# Sheet_DC.net
KiCad netlist of a schematic drawn in Altium Designer
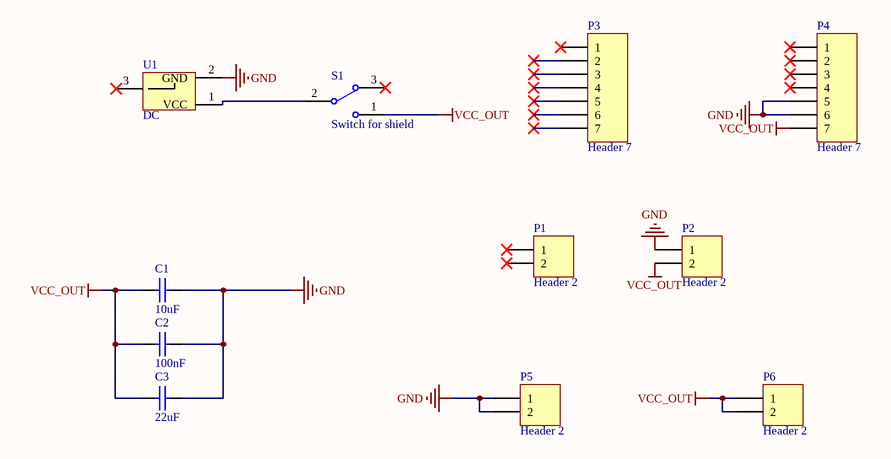
[diagram p0: Sheet_DC.SchDoc]

(export (version "E")
  (design (tool "Eeschema 10.0.6"))
  (components
    (comp (ref "C1")
      (value "10uF")
      (footprint "C0603")
      (description "贴片电容")
      (libsource (lib "Schlib_OLEDMCU") (part "C0603"))
    )
    (comp (ref "C2")
      (value "100nF")
      (footprint "C0603")
      (description "贴片电容")
      (libsource (lib "Schlib_OLEDMCU") (part "C0603"))
    )
    (comp (ref "C3")
      (value "22uF")
      (footprint "C0603")
      (description "贴片电容")
      (libsource (lib "Schlib_OLEDMCU") (part "C0603"))
    )
    (comp (ref "P1")
      (value "Header 2")
      (footprint "HDR1X2")
      (description "Header, 2-Pin")
      (fields (field (name "PUBLISHER") "Altium Limited"))
      (libsource (lib "Miscellaneous Connectors") (part "Header 2"))
    )
    (comp (ref "P2")
      (value "Header 2")
      (footprint "HDR1X2")
      (description "Header, 2-Pin")
      (fields (field (name "PUBLISHER") "Altium Limited"))
      (libsource (lib "Miscellaneous Connectors") (part "Header 2"))
    )
    (comp (ref "P3")
      (value "Header 7")
      (footprint "HDR1X7")
      (description "Header, 7-Pin")
      (fields (field (name "PUBLISHER") "Altium Limited"))
      (libsource (lib "Miscellaneous Connectors") (part "Header 7"))
    )
    (comp (ref "P4")
      (value "Header 7")
      (footprint "HDR1X7")
      (description "Header, 7-Pin")
      (fields (field (name "PUBLISHER") "Altium Limited"))
      (libsource (lib "Miscellaneous Connectors") (part "Header 7"))
    )
    (comp (ref "P5")
      (value "Header 2")
      (footprint "HDR1X2")
      (description "Header, 2-Pin")
      (fields (field (name "PUBLISHER") "Altium Limited"))
      (libsource (lib "Miscellaneous Connectors") (part "Header 2"))
    )
    (comp (ref "P6")
      (value "Header 2")
      (footprint "HDR1X2")
      (description "Header, 2-Pin")
      (fields (field (name "PUBLISHER") "Altium Limited"))
      (libsource (lib "Miscellaneous Connectors") (part "Header 2"))
    )
    (comp (ref "S1")
      (value "Switch for shield")
      (footprint "Switch_battery")
      (description "三脚开关")
      (libsource (lib "Schlib_OLEDMCU") (part "Switch_battery"))
    )
    (comp (ref "U1")
      (value "DC")
      (footprint "DC")
      (description "DC插座")
      (libsource (lib "Schlib_OLEDMCU") (part "DC"))
    )
  )
  (nets
    (net (code "1") (name "GND") (class "Default")
      (node (ref "C1") (pin "2") (pinfunction "2_2") (pintype "passive"))
      (node (ref "C2") (pin "2") (pinfunction "2_2") (pintype "passive"))
      (node (ref "C3") (pin "2") (pinfunction "2_2") (pintype "passive"))
      (node (ref "P2") (pin "1") (pinfunction "1_1") (pintype "passive"))
      (node (ref "P4") (pin "5") (pinfunction "5_5") (pintype "passive"))
      (node (ref "P4") (pin "6") (pinfunction "6_6") (pintype "passive"))
      (node (ref "P5") (pin "1") (pinfunction "1_1") (pintype "passive"))
      (node (ref "P5") (pin "2") (pinfunction "2_2") (pintype "passive"))
      (node (ref "U1") (pin "2") (pinfunction "GND_2") (pintype "passive"))
    )
    (net (code "2") (name "Net-(U1-VCC)") (class "Default")
      (node (ref "S1") (pin "2") (pinfunction "2_2") (pintype "passive"))
      (node (ref "U1") (pin "1") (pinfunction "VCC_1") (pintype "passive"))
    )
    (net (code "3") (name "VCC_OUT") (class "Default")
      (node (ref "C1") (pin "1") (pinfunction "1_1") (pintype "passive"))
      (node (ref "C2") (pin "1") (pinfunction "1_1") (pintype "passive"))
      (node (ref "C3") (pin "1") (pinfunction "1_1") (pintype "passive"))
      (node (ref "P2") (pin "2") (pinfunction "2_2") (pintype "passive"))
      (node (ref "P4") (pin "7") (pinfunction "7_7") (pintype "passive"))
      (node (ref "P6") (pin "1") (pinfunction "1_1") (pintype "passive"))
      (node (ref "P6") (pin "2") (pinfunction "2_2") (pintype "passive"))
      (node (ref "S1") (pin "1") (pinfunction "1_1") (pintype "passive"))
    )
    (net (code "4") (name "unconnected-(P1-Pad1)") (class "Default")
      (node (ref "P1") (pin "1") (pinfunction "1_1") (pintype "passive+no_connect"))
    )
    (net (code "5") (name "unconnected-(P1-Pad2)") (class "Default")
      (node (ref "P1") (pin "2") (pinfunction "2_2") (pintype "passive+no_connect"))
    )
    (net (code "6") (name "unconnected-(P3-Pad1)") (class "Default")
      (node (ref "P3") (pin "1") (pinfunction "1_1") (pintype "passive+no_connect"))
    )
    (net (code "7") (name "unconnected-(P3-Pad2)") (class "Default")
      (node (ref "P3") (pin "2") (pinfunction "2_2") (pintype "passive+no_connect"))
    )
    (net (code "8") (name "unconnected-(P3-Pad3)") (class "Default")
      (node (ref "P3") (pin "3") (pinfunction "3_3") (pintype "passive+no_connect"))
    )
    (net (code "9") (name "unconnected-(P3-Pad4)") (class "Default")
      (node (ref "P3") (pin "4") (pinfunction "4_4") (pintype "passive+no_connect"))
    )
    (net (code "10") (name "unconnected-(P3-Pad5)") (class "Default")
      (node (ref "P3") (pin "5") (pinfunction "5_5") (pintype "passive+no_connect"))
    )
    (net (code "11") (name "unconnected-(P3-Pad6)") (class "Default")
      (node (ref "P3") (pin "6") (pinfunction "6_6") (pintype "passive+no_connect"))
    )
    (net (code "12") (name "unconnected-(P3-Pad7)") (class "Default")
      (node (ref "P3") (pin "7") (pinfunction "7_7") (pintype "passive+no_connect"))
    )
    (net (code "13") (name "unconnected-(P4-Pad1)") (class "Default")
      (node (ref "P4") (pin "1") (pinfunction "1_1") (pintype "passive+no_connect"))
    )
    (net (code "14") (name "unconnected-(P4-Pad2)") (class "Default")
      (node (ref "P4") (pin "2") (pinfunction "2_2") (pintype "passive+no_connect"))
    )
    (net (code "15") (name "unconnected-(P4-Pad3)") (class "Default")
      (node (ref "P4") (pin "3") (pinfunction "3_3") (pintype "passive+no_connect"))
    )
    (net (code "16") (name "unconnected-(P4-Pad4)") (class "Default")
      (node (ref "P4") (pin "4") (pinfunction "4_4") (pintype "passive+no_connect"))
    )
    (net (code "17") (name "unconnected-(S1-Pad3)") (class "Default")
      (node (ref "S1") (pin "3") (pinfunction "3_3") (pintype "passive+no_connect"))
    )
    (net (code "18") (name "unconnected-(U1-Bat-Pad3)") (class "Default")
      (node (ref "U1") (pin "3") (pinfunction "Bat_3") (pintype "passive+no_connect"))
    )
  )
)
